# Motor_Output.net
KiCad netlist of a schematic drawn in Altium Designer
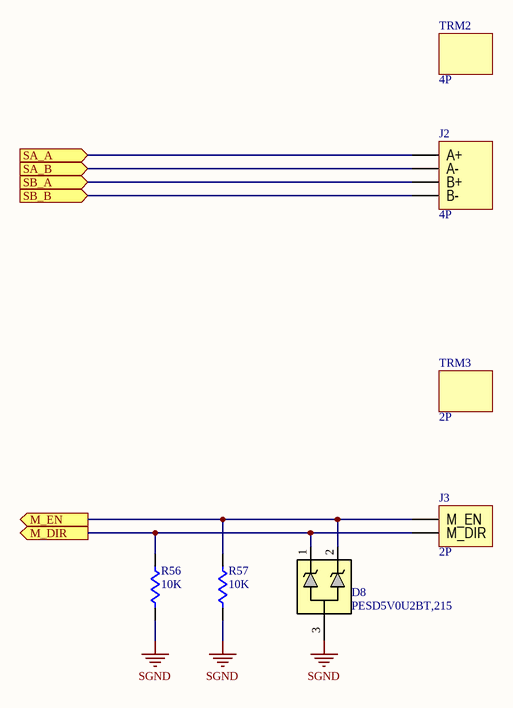
[diagram p0: Motor_Output.SchDoc]

(export (version "E")
  (design (tool "Eeschema 10.0.6"))
  (components
    (comp (ref "D8")
      (value "PESD5V0U2BT,215")
      (footprint "SOT23_3")
      (description "ESD Protection Diodes / TVS Diodes ESD 5V BI")
      (libsource (lib "HZSchLib") (part "PESD5V0U2BT,215"))
    )
    (comp (ref "J2")
      (value "4P")
      (footprint "691313510004")
      (description "Pluggable Terminal Blocks WR-TBL 300VAC 20A 4P Right Angle")
      (libsource (lib "HZSchLib") (part "691313510004"))
    )
    (comp (ref "J3")
      (value "2P")
      (footprint "691313510002")
      (description "Pluggable Terminal Blocks WR-TBL 300VAC 20A 2P Right Angle")
      (libsource (lib "HZSchLib") (part "691313510002"))
    )
    (comp (ref "R56")
      (value "10K")
      (footprint "RES: 0603")
      (description "RES SMD 0603")
      (libsource (lib "HZSchLib") (part "RES 0603"))
    )
    (comp (ref "R57")
      (value "10K")
      (footprint "RES: 0603")
      (description "RES SMD 0603")
      (libsource (lib "HZSchLib") (part "RES 0603"))
    )
    (comp (ref "TRM2")
      (value "4P")
      (description "Pluggable Terminal Blocks WR-TBL 300VAC 20A 4P Right Angle")
      (libsource (lib "HZSchLib") (part "691351500004"))
    )
    (comp (ref "TRM3")
      (value "2P")
      (description "Pluggable Terminal Blocks WR-TBL 300VAC 20A 2P Right Angle")
      (libsource (lib "HZSchLib") (part "691351500002"))
    )
  )
  (nets
    (net (code "1") (name "/M_DIR") (class "Default")
      (node (ref "D8") (pin "1") (pinfunction "K1_1") (pintype "passive"))
      (node (ref "J3") (pin "1") (pinfunction "M_DIR_1") (pintype "passive"))
      (node (ref "R56") (pin "1") (pinfunction "1_1") (pintype "passive"))
    )
    (net (code "2") (name "/M_EN") (class "Default")
      (node (ref "D8") (pin "2") (pinfunction "K2_2") (pintype "passive"))
      (node (ref "J3") (pin "2") (pinfunction "M_EN_2") (pintype "passive"))
      (node (ref "R57") (pin "1") (pinfunction "1_1") (pintype "passive"))
    )
    (net (code "3") (name "/SA_A") (class "Default")
      (node (ref "J2") (pin "1") (pinfunction "A+_1") (pintype "passive"))
    )
    (net (code "4") (name "/SA_B") (class "Default")
      (node (ref "J2") (pin "2") (pinfunction "A-_2") (pintype "passive"))
    )
    (net (code "5") (name "/SB_A") (class "Default")
      (node (ref "J2") (pin "3") (pinfunction "B+_3") (pintype "passive"))
    )
    (net (code "6") (name "/SB_B") (class "Default")
      (node (ref "J2") (pin "4") (pinfunction "B-_4") (pintype "passive"))
    )
    (net (code "7") (name "SGND") (class "Default")
      (node (ref "D8") (pin "3") (pinfunction "CC_3") (pintype "passive"))
      (node (ref "R56") (pin "2") (pinfunction "2_2") (pintype "passive"))
      (node (ref "R57") (pin "2") (pinfunction "2_2") (pintype "passive"))
    )
  )
)
